# amp_tda1557q_v_1_0.net
KiCad netlist of a schematic drawn in EAGLE
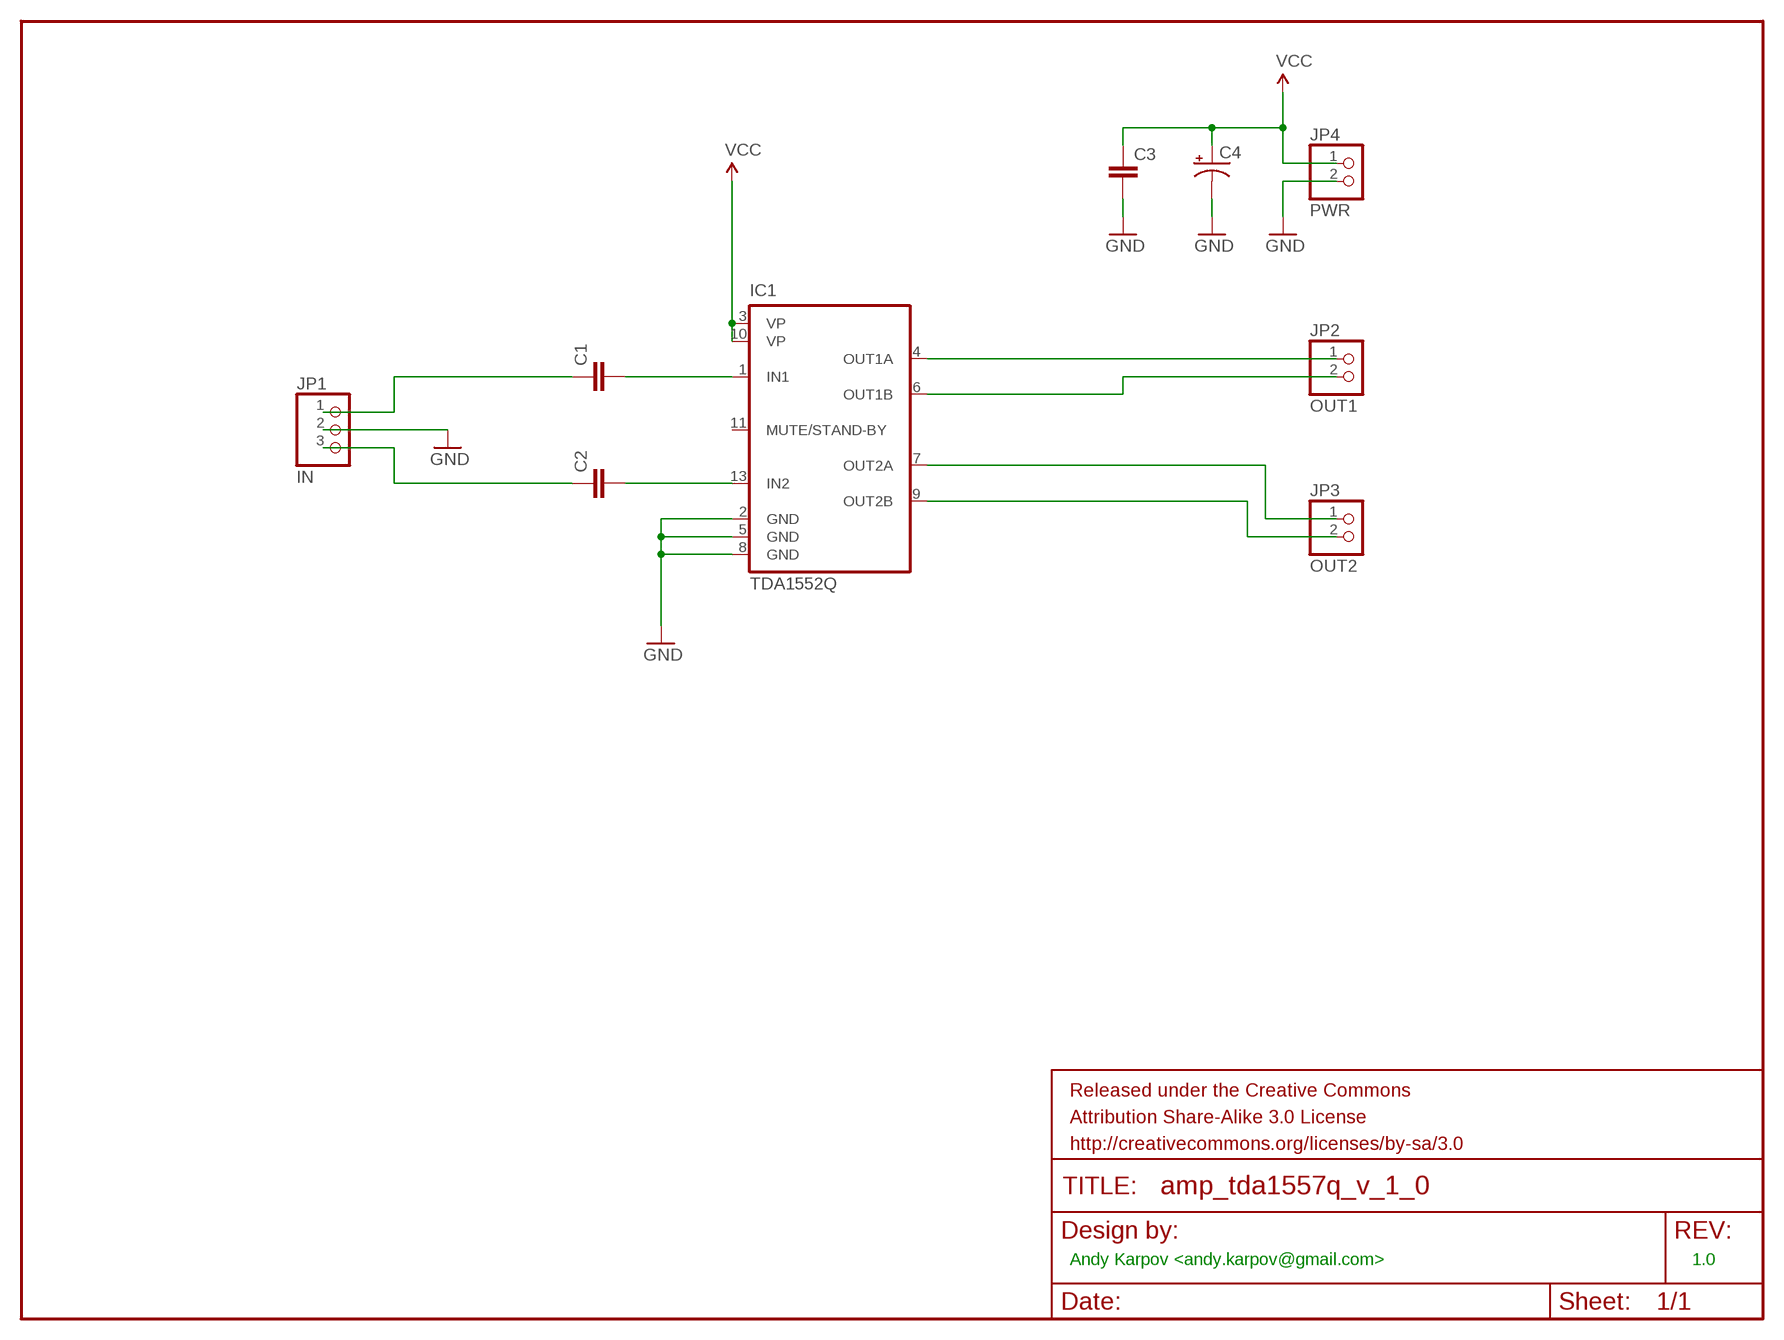
[diagram p0: schematic, sheet 1]

(export (version "E")
  (design (tool "Eeschema 10.0.6"))
  (components
    (comp (ref "C1")
      (value "CAPPTH3")
      (footprint "eagle-import:CAP-PTH-LARGE")
      (libsource (lib "eagle-import") (part "CAPPTH3"))
    )
    (comp (ref "C2")
      (value "CAPPTH3")
      (footprint "eagle-import:CAP-PTH-LARGE")
      (libsource (lib "eagle-import") (part "CAPPTH3"))
    )
    (comp (ref "C3")
      (value "CAPPTH3")
      (footprint "eagle-import:CAP-PTH-LARGE")
      (libsource (lib "eagle-import") (part "CAPPTH3"))
    )
    (comp (ref "C4")
      (value "CAP_POLPTH3")
      (footprint "eagle-import:CPOL-RADIAL-1000UF-63V")
      (libsource (lib "eagle-import") (part "CAP_POLPTH3"))
    )
    (comp (ref "FRAME1")
      (value "FRAME-LETTER")
      (footprint "eagle-import:CREATIVE_COMMONS")
      (libsource (lib "eagle-import") (part "FRAME-LETTER"))
    )
    (comp (ref "IC1")
      (value "TDA1552Q")
      (footprint "eagle-import:MULTIWAT-SIL13")
      (libsource (lib "eagle-import") (part "TDA1552Q"))
    )
    (comp (ref "JP1")
      (value "IN")
      (footprint "eagle-import:1X03")
      (libsource (lib "eagle-import") (part "PINHD-1X3"))
    )
    (comp (ref "JP2")
      (value "OUT1")
      (footprint "eagle-import:1X02")
      (libsource (lib "eagle-import") (part "PINHD-1X2"))
    )
    (comp (ref "JP3")
      (value "OUT2")
      (footprint "eagle-import:1X02")
      (libsource (lib "eagle-import") (part "PINHD-1X2"))
    )
    (comp (ref "JP4")
      (value "PWR")
      (footprint "eagle-import:1X02")
      (libsource (lib "eagle-import") (part "PINHD-1X2"))
    )
  )
  (nets
    (net (code "1") (name "GND") (class "Default")
      (node (ref "C3") (pin "2") (pinfunction "2_2") (pintype "passive"))
      (node (ref "C4") (pin "2") (pinfunction "-_2") (pintype "passive"))
      (node (ref "IC1") (pin "2") (pinfunction "GND_2") (pintype "power_in"))
      (node (ref "IC1") (pin "5") (pinfunction "GND_5") (pintype "power_in"))
      (node (ref "IC1") (pin "8") (pinfunction "GND_8") (pintype "power_in"))
      (node (ref "JP1") (pin "2") (pinfunction "2_2") (pintype "passive"))
      (node (ref "JP4") (pin "2") (pinfunction "2_2") (pintype "passive"))
    )
    (net (code "2") (name "Net-(C1-Pad1)") (class "Default")
      (node (ref "C1") (pin "1") (pinfunction "1_1") (pintype "passive"))
      (node (ref "JP1") (pin "1") (pinfunction "1_1") (pintype "passive"))
    )
    (net (code "3") (name "Net-(C2-Pad1)") (class "Default")
      (node (ref "C2") (pin "1") (pinfunction "1_1") (pintype "passive"))
      (node (ref "JP1") (pin "3") (pinfunction "3_3") (pintype "passive"))
    )
    (net (code "4") (name "Net-(IC1-IN1)") (class "Default")
      (node (ref "C1") (pin "2") (pinfunction "2_2") (pintype "passive"))
      (node (ref "IC1") (pin "1") (pinfunction "IN1_1") (pintype "input"))
    )
    (net (code "5") (name "Net-(IC1-IN2)") (class "Default")
      (node (ref "C2") (pin "2") (pinfunction "2_2") (pintype "passive"))
      (node (ref "IC1") (pin "13") (pinfunction "IN2_13") (pintype "input"))
    )
    (net (code "6") (name "Net-(IC1-OUT1A)") (class "Default")
      (node (ref "IC1") (pin "4") (pinfunction "OUT1A_4") (pintype "output"))
      (node (ref "JP2") (pin "1") (pinfunction "1_1") (pintype "passive"))
    )
    (net (code "7") (name "Net-(IC1-OUT1B)") (class "Default")
      (node (ref "IC1") (pin "6") (pinfunction "OUT1B_6") (pintype "output"))
      (node (ref "JP2") (pin "2") (pinfunction "2_2") (pintype "passive"))
    )
    (net (code "8") (name "Net-(IC1-OUT2A)") (class "Default")
      (node (ref "IC1") (pin "7") (pinfunction "OUT2A_7") (pintype "output"))
      (node (ref "JP3") (pin "1") (pinfunction "1_1") (pintype "passive"))
    )
    (net (code "9") (name "Net-(IC1-OUT2B)") (class "Default")
      (node (ref "IC1") (pin "9") (pinfunction "OUT2B_9") (pintype "output"))
      (node (ref "JP3") (pin "2") (pinfunction "2_2") (pintype "passive"))
    )
    (net (code "10") (name "VCC") (class "Default")
      (node (ref "C3") (pin "1") (pinfunction "1_1") (pintype "passive"))
      (node (ref "C4") (pin "1") (pinfunction "+_1") (pintype "passive"))
      (node (ref "IC1") (pin "10") (pinfunction "VP_10") (pintype "input"))
      (node (ref "IC1") (pin "3") (pinfunction "VP_3") (pintype "input"))
      (node (ref "JP4") (pin "1") (pinfunction "1_1") (pintype "passive"))
    )
    (net (code "11") (name "unconnected-(IC1-MUTE{slash}STAND-BY-Pad11)") (class "Default")
      (node (ref "IC1") (pin "11") (pinfunction "MUTE/STAND-BY_11") (pintype "input"))
    )
  )
)
